# module.net
KiCad netlist of a schematic drawn in EAGLE
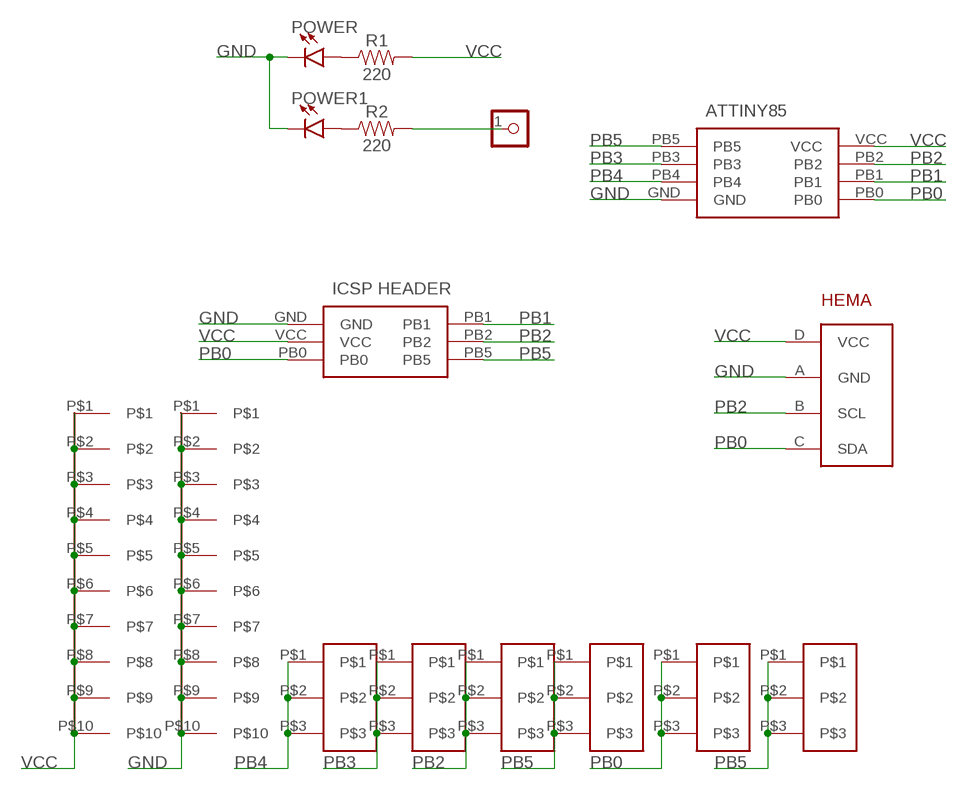
[diagram p0: schematic, sheet 1]

(export (version "E")
  (design (tool "Eeschema 10.0.6"))
  (components
    (comp (ref "0")
      (value "3X-PADS-CONNECTED")
      (footprint "eagle-import:3X-PADS")
      (libsource (lib "eagle-import") (part "3X-PADS-CONNECTED"))
    )
    (comp (ref "1")
      (value "3X-PADS-CONNECTED")
      (footprint "eagle-import:3X-PADS")
      (libsource (lib "eagle-import") (part "3X-PADS-CONNECTED"))
    )
    (comp (ref "2")
      (value "3X-PADS-CONNECTED")
      (footprint "eagle-import:3X-PADS")
      (libsource (lib "eagle-import") (part "3X-PADS-CONNECTED"))
    )
    (comp (ref "3")
      (value "3X-PADS-CONNECTED")
      (footprint "eagle-import:3X-PADS")
      (libsource (lib "eagle-import") (part "3X-PADS-CONNECTED"))
    )
    (comp (ref "4")
      (value "3X-PADS-CONNECTED")
      (footprint "eagle-import:3X-PADS")
      (libsource (lib "eagle-import") (part "3X-PADS-CONNECTED"))
    )
    (comp (ref "5")
      (value "3X-PADS-CONNECTED")
      (footprint "eagle-import:3X-PADS")
      (libsource (lib "eagle-import") (part "3X-PADS-CONNECTED"))
    )
    (comp (ref "GND")
      (value "10X-PADS")
      (footprint "eagle-import:10X-PADS")
      (libsource (lib "eagle-import") (part "10X-PADS"))
    )
    (comp (ref "IC1")
      (value "ATTINY85-20SU")
      (footprint "eagle-import:SOT127P798X216-8N")
      (fields (field (name "RS_PART_NUMBER") "1331674"))
      (libsource (lib "eagle-import") (part "ATTINY85-20SU"))
    )
    (comp (ref "J1")
      (value "M20-9980346")
      (footprint "eagle-import:HDRV6W64P254_2X3_762X508X868P")
      (fields (field (name "RS_PART_NUMBER") "7457046P"))
      (libsource (lib "eagle-import") (part "M20-9980346"))
    )
    (comp (ref "P1")
      (value "PROTO_VIAS_01X01-1.2")
      (footprint "eagle-import:PROTO_VIAS_01X01_1.2")
      (libsource (lib "eagle-import") (part "PROTO_VIAS_01X01-1.2"))
    )
    (comp (ref "POWER")
      (value "LED3MM")
      (footprint "eagle-import:LED_3MM")
      (libsource (lib "eagle-import") (part "LED3MM"))
    )
    (comp (ref "POWER1")
      (value "LED3MM")
      (footprint "eagle-import:LED_3MM")
      (libsource (lib "eagle-import") (part "LED3MM"))
    )
    (comp (ref "R1")
      (value "220")
      (footprint "eagle-import:AXIAL-0.3")
      (libsource (lib "eagle-import") (part "RESISTORAXIAL-0.3"))
    )
    (comp (ref "R2")
      (value "220")
      (footprint "eagle-import:AXIAL-0.3")
      (libsource (lib "eagle-import") (part "RESISTORAXIAL-0.3"))
    )
    (comp (ref "U$1")
      (value "HEMA-I2C")
      (footprint "eagle-import:HEMA-I2C")
      (libsource (lib "eagle-import") (part "HEMA-I2C"))
    )
    (comp (ref "VCC")
      (value "10X-PADS")
      (footprint "eagle-import:10X-PADS")
      (libsource (lib "eagle-import") (part "10X-PADS"))
    )
  )
  (nets
    (net (code "1") (name "/GND") (class "Default")
      (node (ref "GND") (pin "P$1") (pinfunction "P$1_P$1") (pintype "bidirectional"))
      (node (ref "GND") (pin "P$10") (pinfunction "P$10_P$10") (pintype "bidirectional"))
      (node (ref "GND") (pin "P$2") (pinfunction "P$2_P$2") (pintype "bidirectional"))
      (node (ref "GND") (pin "P$3") (pinfunction "P$3_P$3") (pintype "bidirectional"))
      (node (ref "GND") (pin "P$4") (pinfunction "P$4_P$4") (pintype "bidirectional"))
      (node (ref "GND") (pin "P$5") (pinfunction "P$5_P$5") (pintype "bidirectional"))
      (node (ref "GND") (pin "P$6") (pinfunction "P$6_P$6") (pintype "bidirectional"))
      (node (ref "GND") (pin "P$7") (pinfunction "P$7_P$7") (pintype "bidirectional"))
      (node (ref "GND") (pin "P$8") (pinfunction "P$8_P$8") (pintype "bidirectional"))
      (node (ref "GND") (pin "P$9") (pinfunction "P$9_P$9") (pintype "bidirectional"))
      (node (ref "IC1") (pin "GND") (pinfunction "GND_GND") (pintype "bidirectional"))
      (node (ref "J1") (pin "GND") (pinfunction "GND_GND") (pintype "bidirectional"))
      (node (ref "POWER") (pin "K") (pinfunction "C_K") (pintype "passive"))
      (node (ref "POWER1") (pin "K") (pinfunction "C_K") (pintype "passive"))
      (node (ref "U$1") (pin "A") (pinfunction "GND_A") (pintype "bidirectional"))
    )
    (net (code "2") (name "/PB0") (class "Default")
      (node (ref "0") (pin "P$1") (pinfunction "P$1_P$1") (pintype "bidirectional"))
      (node (ref "0") (pin "P$2") (pinfunction "P$2_P$2") (pintype "bidirectional"))
      (node (ref "0") (pin "P$3") (pinfunction "P$3_P$3") (pintype "bidirectional"))
      (node (ref "IC1") (pin "PB0") (pinfunction "PB0_PB0") (pintype "bidirectional"))
      (node (ref "J1") (pin "PB0") (pinfunction "PB0_PB0") (pintype "bidirectional"))
      (node (ref "U$1") (pin "C") (pinfunction "SDA_C") (pintype "bidirectional"))
    )
    (net (code "3") (name "/PB1") (class "Default")
      (node (ref "IC1") (pin "PB1") (pinfunction "PB1_PB1") (pintype "bidirectional"))
      (node (ref "J1") (pin "PB1") (pinfunction "PB1_PB1") (pintype "bidirectional"))
    )
    (net (code "4") (name "/PB2") (class "Default")
      (node (ref "2") (pin "P$1") (pinfunction "P$1_P$1") (pintype "bidirectional"))
      (node (ref "2") (pin "P$2") (pinfunction "P$2_P$2") (pintype "bidirectional"))
      (node (ref "2") (pin "P$3") (pinfunction "P$3_P$3") (pintype "bidirectional"))
      (node (ref "IC1") (pin "PB2") (pinfunction "PB2_PB2") (pintype "bidirectional"))
      (node (ref "J1") (pin "PB2") (pinfunction "PB2_PB2") (pintype "bidirectional"))
      (node (ref "U$1") (pin "B") (pinfunction "SCL_B") (pintype "bidirectional"))
    )
    (net (code "5") (name "/PB3") (class "Default")
      (node (ref "3") (pin "P$1") (pinfunction "P$1_P$1") (pintype "bidirectional"))
      (node (ref "3") (pin "P$2") (pinfunction "P$2_P$2") (pintype "bidirectional"))
      (node (ref "3") (pin "P$3") (pinfunction "P$3_P$3") (pintype "bidirectional"))
      (node (ref "IC1") (pin "PB3") (pinfunction "PB3_PB3") (pintype "bidirectional"))
    )
    (net (code "6") (name "/PB4") (class "Default")
      (node (ref "4") (pin "P$1") (pinfunction "P$1_P$1") (pintype "bidirectional"))
      (node (ref "4") (pin "P$2") (pinfunction "P$2_P$2") (pintype "bidirectional"))
      (node (ref "4") (pin "P$3") (pinfunction "P$3_P$3") (pintype "bidirectional"))
      (node (ref "IC1") (pin "PB4") (pinfunction "PB4_PB4") (pintype "bidirectional"))
    )
    (net (code "7") (name "/PB5") (class "Default")
      (node (ref "1") (pin "P$1") (pinfunction "P$1_P$1") (pintype "bidirectional"))
      (node (ref "1") (pin "P$2") (pinfunction "P$2_P$2") (pintype "bidirectional"))
      (node (ref "1") (pin "P$3") (pinfunction "P$3_P$3") (pintype "bidirectional"))
      (node (ref "5") (pin "P$1") (pinfunction "P$1_P$1") (pintype "bidirectional"))
      (node (ref "5") (pin "P$2") (pinfunction "P$2_P$2") (pintype "bidirectional"))
      (node (ref "5") (pin "P$3") (pinfunction "P$3_P$3") (pintype "bidirectional"))
      (node (ref "IC1") (pin "PB5") (pinfunction "PB5_PB5") (pintype "bidirectional"))
      (node (ref "J1") (pin "PB5") (pinfunction "PB5_PB5") (pintype "bidirectional"))
    )
    (net (code "8") (name "/VCC") (class "Default")
      (node (ref "IC1") (pin "VCC") (pinfunction "VCC_VCC") (pintype "bidirectional"))
      (node (ref "J1") (pin "VCC") (pinfunction "VCC_VCC") (pintype "bidirectional"))
      (node (ref "R1") (pin "P$2") (pinfunction "2_P$2") (pintype "passive"))
      (node (ref "U$1") (pin "D") (pinfunction "VCC_D") (pintype "bidirectional"))
      (node (ref "VCC") (pin "P$1") (pinfunction "P$1_P$1") (pintype "bidirectional"))
      (node (ref "VCC") (pin "P$10") (pinfunction "P$10_P$10") (pintype "bidirectional"))
      (node (ref "VCC") (pin "P$2") (pinfunction "P$2_P$2") (pintype "bidirectional"))
      (node (ref "VCC") (pin "P$3") (pinfunction "P$3_P$3") (pintype "bidirectional"))
      (node (ref "VCC") (pin "P$4") (pinfunction "P$4_P$4") (pintype "bidirectional"))
      (node (ref "VCC") (pin "P$5") (pinfunction "P$5_P$5") (pintype "bidirectional"))
      (node (ref "VCC") (pin "P$6") (pinfunction "P$6_P$6") (pintype "bidirectional"))
      (node (ref "VCC") (pin "P$7") (pinfunction "P$7_P$7") (pintype "bidirectional"))
      (node (ref "VCC") (pin "P$8") (pinfunction "P$8_P$8") (pintype "bidirectional"))
      (node (ref "VCC") (pin "P$9") (pinfunction "P$9_P$9") (pintype "bidirectional"))
    )
    (net (code "9") (name "Net-(R1-1)") (class "Default")
      (node (ref "POWER") (pin "A") (pinfunction "A_A") (pintype "passive"))
      (node (ref "R1") (pin "P$1") (pinfunction "1_P$1") (pintype "passive"))
    )
    (net (code "10") (name "Net-(R2-1)") (class "Default")
      (node (ref "POWER1") (pin "A") (pinfunction "A_A") (pintype "passive"))
      (node (ref "R2") (pin "P$1") (pinfunction "1_P$1") (pintype "passive"))
    )
    (net (code "11") (name "Net-(R2-2)") (class "Default")
      (node (ref "P1") (pin "1") (pinfunction "1_1") (pintype "passive"))
      (node (ref "R2") (pin "P$2") (pinfunction "2_P$2") (pintype "passive"))
    )
  )
)
